# Front_PCB.net
KiCad netlist of a schematic drawn in EAGLE
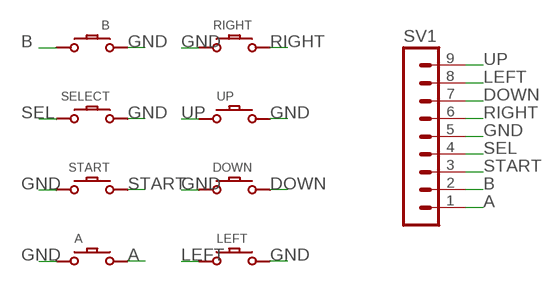
[diagram p0: schematic, sheet 1]

(export (version "E")
  (design (tool "Eeschema 10.0.6"))
  (components
    (comp (ref "A")
      (value "DMG-BTN")
      (footprint "eagle-import:DMG-BTN")
      (libsource (lib "eagle-import") (part "DMG-BTNREGULAR"))
    )
    (comp (ref "B")
      (value "DMG-BTN")
      (footprint "eagle-import:DMG-BTN")
      (libsource (lib "eagle-import") (part "DMG-BTNREGULAR"))
    )
    (comp (ref "DOWN")
      (value "DMG-BTN")
      (footprint "eagle-import:DMG-BTN")
      (libsource (lib "eagle-import") (part "DMG-BTNREGULAR"))
    )
    (comp (ref "LEFT")
      (value "DMG-BTN")
      (footprint "eagle-import:DMG-BTN")
      (libsource (lib "eagle-import") (part "DMG-BTNREGULAR"))
    )
    (comp (ref "RIGHT")
      (value "DMG-BTN")
      (footprint "eagle-import:DMG-BTN")
      (libsource (lib "eagle-import") (part "DMG-BTNREGULAR"))
    )
    (comp (ref "SELECT")
      (value "DMG-BTN")
      (footprint "eagle-import:DMG-SEL")
      (libsource (lib "eagle-import") (part "DMG-BTNSELECT"))
    )
    (comp (ref "START")
      (value "DMG-BTN")
      (footprint "eagle-import:DMG-ST")
      (libsource (lib "eagle-import") (part "DMG-BTNSTART"))
    )
    (comp (ref "SV1")
      (value "MA09-1")
      (footprint "eagle-import:MA09-1")
      (libsource (lib "eagle-import") (part "MA09-1"))
    )
    (comp (ref "UP")
      (value "DMG-BTN")
      (footprint "eagle-import:DMG-BTN")
      (libsource (lib "eagle-import") (part "DMG-BTNREGULAR"))
    )
  )
  (nets
    (net (code "1") (name "/A") (class "Default")
      (node (ref "A") (pin "P$2") (pinfunction "P$2_P$2") (pintype "bidirectional"))
      (node (ref "SV1") (pin "1") (pinfunction "1_1") (pintype "passive"))
    )
    (net (code "2") (name "/B") (class "Default")
      (node (ref "B") (pin "P$2") (pinfunction "P$2_P$2") (pintype "bidirectional"))
      (node (ref "SV1") (pin "2") (pinfunction "2_2") (pintype "passive"))
    )
    (net (code "3") (name "/DOWN") (class "Default")
      (node (ref "DOWN") (pin "P$1") (pinfunction "P$1_P$1") (pintype "bidirectional"))
      (node (ref "SV1") (pin "7") (pinfunction "7_7") (pintype "passive"))
    )
    (net (code "4") (name "/GND") (class "Default")
      (node (ref "A") (pin "P$1") (pinfunction "P$1_P$1") (pintype "bidirectional"))
      (node (ref "B") (pin "P$1") (pinfunction "P$1_P$1") (pintype "bidirectional"))
      (node (ref "DOWN") (pin "P$2") (pinfunction "P$2_P$2") (pintype "bidirectional"))
      (node (ref "LEFT") (pin "P$2") (pinfunction "P$2_P$2") (pintype "bidirectional"))
      (node (ref "RIGHT") (pin "P$2") (pinfunction "P$2_P$2") (pintype "bidirectional"))
      (node (ref "SELECT") (pin "P$1") (pinfunction "P$1_P$1") (pintype "bidirectional"))
      (node (ref "START") (pin "P$2") (pinfunction "P$2_P$2") (pintype "bidirectional"))
      (node (ref "SV1") (pin "5") (pinfunction "5_5") (pintype "passive"))
      (node (ref "UP") (pin "P$2") (pinfunction "P$2_P$2") (pintype "bidirectional"))
    )
    (net (code "5") (name "/LEFT") (class "Default")
      (node (ref "LEFT") (pin "P$1") (pinfunction "P$1_P$1") (pintype "bidirectional"))
      (node (ref "SV1") (pin "8") (pinfunction "8_8") (pintype "passive"))
    )
    (net (code "6") (name "/RIGHT") (class "Default")
      (node (ref "RIGHT") (pin "P$1") (pinfunction "P$1_P$1") (pintype "bidirectional"))
      (node (ref "SV1") (pin "6") (pinfunction "6_6") (pintype "passive"))
    )
    (net (code "7") (name "/SEL") (class "Default")
      (node (ref "SELECT") (pin "P$2") (pinfunction "P$2_P$2") (pintype "bidirectional"))
      (node (ref "SV1") (pin "4") (pinfunction "4_4") (pintype "passive"))
    )
    (net (code "8") (name "/START") (class "Default")
      (node (ref "START") (pin "P$1") (pinfunction "P$1_P$1") (pintype "bidirectional"))
      (node (ref "SV1") (pin "3") (pinfunction "3_3") (pintype "passive"))
    )
    (net (code "9") (name "/UP") (class "Default")
      (node (ref "SV1") (pin "9") (pinfunction "9_9") (pintype "passive"))
      (node (ref "UP") (pin "P$1") (pinfunction "P$1_P$1") (pintype "bidirectional"))
    )
  )
)
